# power.net
KiCad netlist of a schematic drawn in Altium Designer
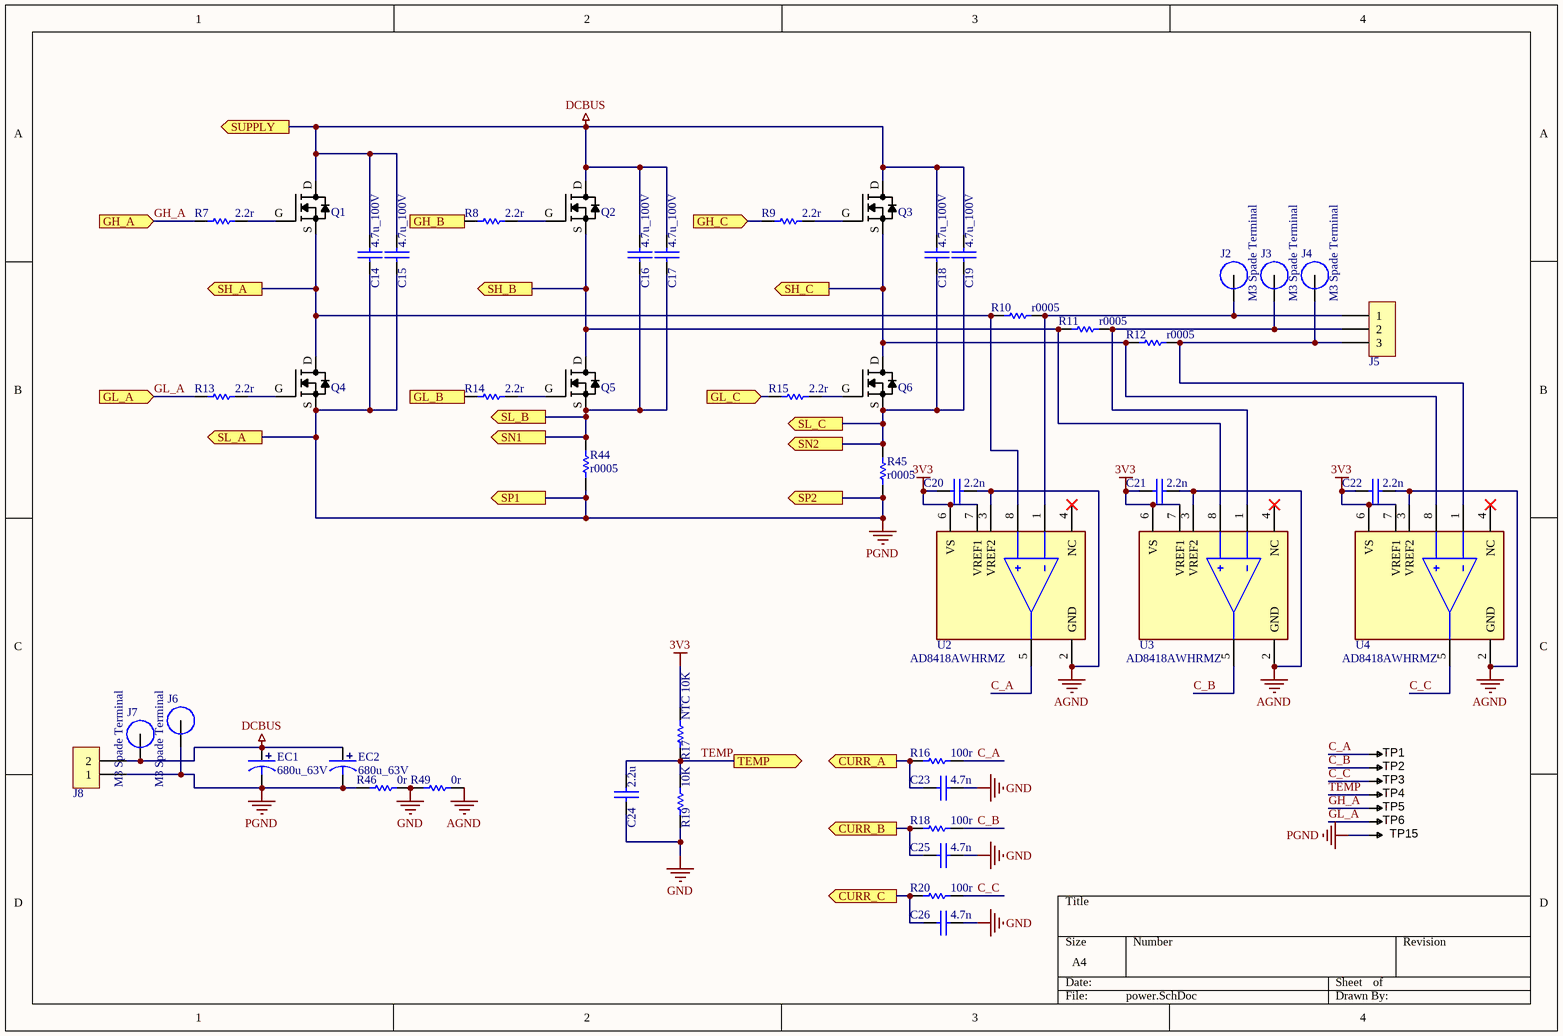
[diagram p0: power.SchDoc]

(export (version "E")
  (design (tool "Eeschema 10.0.6"))
  (components
    (comp (ref "C14")
      (value "4.7u_100V")
      (footprint "1206C")
      (description "无极性电容")
      (libsource (lib "电容") (part "CAP"))
    )
    (comp (ref "C15")
      (value "4.7u_100V")
      (footprint "1206C")
      (description "无极性电容")
      (libsource (lib "电容") (part "CAP"))
    )
    (comp (ref "C16")
      (value "4.7u_100V")
      (footprint "1206C")
      (description "无极性电容")
      (libsource (lib "电容") (part "CAP"))
    )
    (comp (ref "C17")
      (value "4.7u_100V")
      (footprint "1206C")
      (description "无极性电容")
      (libsource (lib "电容") (part "CAP"))
    )
    (comp (ref "C18")
      (value "4.7u_100V")
      (footprint "1206C")
      (description "无极性电容")
      (libsource (lib "电容") (part "CAP"))
    )
    (comp (ref "C19")
      (value "4.7u_100V")
      (footprint "1206C")
      (description "无极性电容")
      (libsource (lib "电容") (part "CAP"))
    )
    (comp (ref "C20")
      (value "2.2n")
      (footprint "0603C")
      (description "无极性电容")
      (libsource (lib "电容") (part "CAP"))
    )
    (comp (ref "C21")
      (value "2.2n")
      (footprint "0603C")
      (description "无极性电容")
      (libsource (lib "电容") (part "CAP"))
    )
    (comp (ref "C22")
      (value "2.2n")
      (footprint "0603C")
      (description "无极性电容")
      (libsource (lib "电容") (part "CAP"))
    )
    (comp (ref "C23")
      (value "4.7n")
      (footprint "0603C")
      (description "无极性电容")
      (libsource (lib "电容") (part "CAP"))
    )
    (comp (ref "C24")
      (value "2.2u")
      (footprint "0603C")
      (description "无极性电容")
      (libsource (lib "电容") (part "CAP"))
    )
    (comp (ref "C25")
      (value "4.7n")
      (footprint "0603C")
      (description "无极性电容")
      (libsource (lib "电容") (part "CAP"))
    )
    (comp (ref "C26")
      (value "4.7n")
      (footprint "0603C")
      (description "无极性电容")
      (libsource (lib "电容") (part "CAP"))
    )
    (comp (ref "EC1")
      (value "680u_63V")
      (footprint "DIP-EC5.0X12.5X25")
      (description "直插电解电容")
      (libsource (lib "电容") (part "DIP_ECAP"))
    )
    (comp (ref "EC2")
      (value "680u_63V")
      (footprint "DIP-EC5.0X12.5X25")
      (description "直插电解电容")
      (libsource (lib "电容") (part "DIP_ECAP"))
    )
    (comp (ref "J2")
      (value "M3 Spade Terminal")
      (footprint "M3 Spade Hole")
      (libsource (lib "two_ax_PCB") (part "M3 Spade Terminal"))
    )
    (comp (ref "J3")
      (value "M3 Spade Terminal")
      (footprint "M3 Spade Hole")
      (libsource (lib "two_ax_PCB") (part "M3 Spade Terminal"))
    )
    (comp (ref "J4")
      (value "M3 Spade Terminal")
      (footprint "M3 Spade Hole")
      (libsource (lib "two_ax_PCB") (part "M3 Spade Terminal"))
    )
    (comp (ref "J5")
      (value "1704936")
      (footprint "1704936")
      (description "CONN TERM BLOCK 3POS 7.62MM")
      (fields (field (name "MANUFACTURER") "Phoenix Contact") (field (name "VOLTAGE") "300V"))
      (libsource (lib "two_ax_PCB") (part "1704936"))
    )
    (comp (ref "J6")
      (value "M3 Spade Terminal")
      (footprint "M3 Spade Hole")
      (libsource (lib "two_ax_PCB") (part "M3 Spade Terminal"))
    )
    (comp (ref "J7")
      (value "M3 Spade Terminal")
      (footprint "M3 Spade Hole")
      (libsource (lib "two_ax_PCB") (part "M3 Spade Terminal"))
    )
    (comp (ref "J8")
      (value "1868076")
      (footprint "1868076")
      (description "CONN TERM BLOCK 2POS 7.62MM")
      (fields (field (name "MANUFACTURER") "Phoenix Contact") (field (name "VOLTAGE") "300V"))
      (libsource (lib "two_ax_PCB") (part "1868076"))
    )
    (comp (ref "Q1")
      (value "FILL_FOOTPRINT")
      (footprint "SO8FL_VIAS")
      (description "MOSFET N-CH 30V 13A SO8FL")
      (fields
        (field (name "MANUFACTURER") "ON Semiconductor")
        (field (name "MANUFACTURER PART NUMBER") "NTMFS4935NT1G")
      )
      (libsource (lib "two_ax_PCB") (part "NTMFS4935NT1G_1"))
    )
    (comp (ref "Q2")
      (value "FILL_FOOTPRINT")
      (footprint "SO8FL_VIAS")
      (description "MOSFET N-CH 30V 13A SO8FL")
      (fields
        (field (name "MANUFACTURER") "ON Semiconductor")
        (field (name "MANUFACTURER PART NUMBER") "NTMFS4935NT1G")
      )
      (libsource (lib "two_ax_PCB") (part "NTMFS4935NT1G_1"))
    )
    (comp (ref "Q3")
      (value "FILL_FOOTPRINT")
      (footprint "SO8FL_VIAS")
      (description "MOSFET N-CH 30V 13A SO8FL")
      (fields
        (field (name "MANUFACTURER") "ON Semiconductor")
        (field (name "MANUFACTURER PART NUMBER") "NTMFS4935NT1G")
      )
      (libsource (lib "two_ax_PCB") (part "NTMFS4935NT1G_1"))
    )
    (comp (ref "Q4")
      (value "FILL_FOOTPRINT")
      (footprint "SO8FL_VIAS")
      (description "MOSFET N-CH 30V 13A SO8FL")
      (fields
        (field (name "MANUFACTURER") "ON Semiconductor")
        (field (name "MANUFACTURER PART NUMBER") "NTMFS4935NT1G")
      )
      (libsource (lib "two_ax_PCB") (part "NTMFS4935NT1G_1"))
    )
    (comp (ref "Q5")
      (value "FILL_FOOTPRINT")
      (footprint "SO8FL_VIAS")
      (description "MOSFET N-CH 30V 13A SO8FL")
      (fields
        (field (name "MANUFACTURER") "ON Semiconductor")
        (field (name "MANUFACTURER PART NUMBER") "NTMFS4935NT1G")
      )
      (libsource (lib "two_ax_PCB") (part "NTMFS4935NT1G_1"))
    )
    (comp (ref "Q6")
      (value "FILL_FOOTPRINT")
      (footprint "SO8FL_VIAS")
      (description "MOSFET N-CH 30V 13A SO8FL")
      (fields
        (field (name "MANUFACTURER") "ON Semiconductor")
        (field (name "MANUFACTURER PART NUMBER") "NTMFS4935NT1G")
      )
      (libsource (lib "two_ax_PCB") (part "NTMFS4935NT1G_1"))
    )
    (comp (ref "R7") (value "2.2r") (footprint "0603R") (libsource (lib "电阻") (part "RES")))
    (comp (ref "R8") (value "2.2r") (footprint "0603R") (libsource (lib "电阻") (part "RES")))
    (comp (ref "R9") (value "2.2r") (footprint "0603R") (libsource (lib "电阻") (part "RES")))
    (comp (ref "R10") (value "r0005") (footprint "2512R") (libsource (lib "电阻") (part "RES")))
    (comp (ref "R11") (value "r0005") (footprint "2512R") (libsource (lib "电阻") (part "RES")))
    (comp (ref "R12") (value "r0005") (footprint "2512R") (libsource (lib "电阻") (part "RES")))
    (comp (ref "R13") (value "2.2r") (footprint "0603R") (libsource (lib "电阻") (part "RES")))
    (comp (ref "R14") (value "2.2r") (footprint "0603R") (libsource (lib "电阻") (part "RES")))
    (comp (ref "R15") (value "2.2r") (footprint "0603R") (libsource (lib "电阻") (part "RES")))
    (comp (ref "R16") (value "100r") (footprint "0603R") (libsource (lib "电阻") (part "RES")))
    (comp (ref "R17") (value "NTC 10K") (footprint "0603R") (libsource (lib "电阻") (part "RES")))
    (comp (ref "R18") (value "100r") (footprint "0603R") (libsource (lib "电阻") (part "RES")))
    (comp (ref "R19") (value "10K") (footprint "0603R") (libsource (lib "电阻") (part "RES")))
    (comp (ref "R20") (value "100r") (footprint "0603R") (libsource (lib "电阻") (part "RES")))
    (comp (ref "R44") (value "r0005") (footprint "2512R") (libsource (lib "电阻") (part "RES")))
    (comp (ref "R45") (value "r0005") (footprint "2512R") (libsource (lib "电阻") (part "RES")))
    (comp (ref "R46") (value "0r") (footprint "0603R") (libsource (lib "电阻") (part "RES")))
    (comp (ref "R49") (value "0r") (footprint "0603R") (libsource (lib "电阻") (part "RES")))
    (comp (ref "TP1")
      (value "TESTPOINT")
      (footprint "FIDUCIAL")
      (description "SMD test pin")
      (libsource (lib "two_ax_PCB") (part "TESTPOINT"))
    )
    (comp (ref "TP2")
      (value "TESTPOINT")
      (footprint "FIDUCIAL")
      (description "SMD test pin")
      (libsource (lib "two_ax_PCB") (part "TESTPOINT"))
    )
    (comp (ref "TP3")
      (value "TESTPOINT")
      (footprint "FIDUCIAL")
      (description "SMD test pin")
      (libsource (lib "two_ax_PCB") (part "TESTPOINT"))
    )
    (comp (ref "TP4")
      (value "TESTPOINT")
      (footprint "FIDUCIAL")
      (description "SMD test pin")
      (libsource (lib "two_ax_PCB") (part "TESTPOINT"))
    )
    (comp (ref "TP5")
      (value "TESTPOINT")
      (footprint "FIDUCIAL")
      (description "SMD test pin")
      (libsource (lib "two_ax_PCB") (part "TESTPOINT"))
    )
    (comp (ref "TP6")
      (value "TESTPOINT")
      (footprint "FIDUCIAL")
      (description "SMD test pin")
      (libsource (lib "two_ax_PCB") (part "TESTPOINT"))
    )
    (comp (ref "TP15")
      (value "TESTPOINT")
      (footprint "FIDUCIAL")
      (description "SMD test pin")
      (libsource (lib "two_ax_PCB") (part "TESTPOINT"))
    )
    (comp (ref "U2")
      (value "AD8418AWHRMZ")
      (footprint "FP-RM-8-IPC_A")
      (description "IC CURR SENSE 1 CIRCUIT 8MSOP")
      (libsource (lib "Altium Content Vault") (part "e0672f2e4abe77d2531f0930e625d4f"))
    )
    (comp (ref "U3")
      (value "AD8418AWHRMZ")
      (footprint "FP-RM-8-IPC_A")
      (description "IC CURR SENSE 1 CIRCUIT 8MSOP")
      (libsource (lib "Altium Content Vault") (part "e0672f2e4abe77d2531f0930e625d4f"))
    )
    (comp (ref "U4")
      (value "AD8418AWHRMZ")
      (footprint "FP-RM-8-IPC_A")
      (description "IC CURR SENSE 1 CIRCUIT 8MSOP")
      (libsource (lib "Altium Content Vault") (part "e0672f2e4abe77d2531f0930e625d4f"))
    )
  )
  (nets
    (net (code "1") (name "/CURR_A") (class "Default")
      (node (ref "C23") (pin "2") (pinfunction "2_2") (pintype "passive"))
      (node (ref "R16") (pin "2") (pinfunction "2_2") (pintype "passive"))
    )
    (net (code "2") (name "/CURR_B") (class "Default")
      (node (ref "C25") (pin "2") (pinfunction "2_2") (pintype "passive"))
      (node (ref "R18") (pin "2") (pinfunction "2_2") (pintype "passive"))
    )
    (net (code "3") (name "/CURR_C") (class "Default")
      (node (ref "C26") (pin "2") (pinfunction "2_2") (pintype "passive"))
      (node (ref "R20") (pin "2") (pinfunction "2_2") (pintype "passive"))
    )
    (net (code "4") (name "/C_A") (class "Default")
      (node (ref "R16") (pin "1") (pinfunction "1_1") (pintype "passive"))
      (node (ref "TP1") (pin "1") (pintype "passive"))
      (node (ref "U2") (pin "5") (pinfunction "OUT_5") (pintype "passive"))
    )
    (net (code "5") (name "/C_B") (class "Default")
      (node (ref "R18") (pin "1") (pinfunction "1_1") (pintype "passive"))
      (node (ref "TP2") (pin "1") (pintype "passive"))
      (node (ref "U3") (pin "5") (pinfunction "OUT_5") (pintype "passive"))
    )
    (net (code "6") (name "/C_C") (class "Default")
      (node (ref "R20") (pin "1") (pinfunction "1_1") (pintype "passive"))
      (node (ref "TP3") (pin "1") (pintype "passive"))
      (node (ref "U4") (pin "5") (pinfunction "OUT_5") (pintype "passive"))
    )
    (net (code "7") (name "/GH_A") (class "Default")
      (node (ref "R7") (pin "1") (pinfunction "1_1") (pintype "passive"))
      (node (ref "TP5") (pin "1") (pintype "passive"))
    )
    (net (code "8") (name "/GH_B") (class "Default")
      (node (ref "R8") (pin "1") (pinfunction "1_1") (pintype "passive"))
    )
    (net (code "9") (name "/GH_C") (class "Default")
      (node (ref "R9") (pin "1") (pinfunction "1_1") (pintype "passive"))
    )
    (net (code "10") (name "/GL_A") (class "Default")
      (node (ref "R13") (pin "1") (pinfunction "1_1") (pintype "passive"))
      (node (ref "TP6") (pin "1") (pintype "passive"))
    )
    (net (code "11") (name "/GL_B") (class "Default")
      (node (ref "R14") (pin "1") (pinfunction "1_1") (pintype "passive"))
    )
    (net (code "12") (name "/GL_C") (class "Default")
      (node (ref "R15") (pin "1") (pinfunction "1_1") (pintype "passive"))
    )
    (net (code "13") (name "/SH_A") (class "Default")
      (node (ref "Q1") (pin "S") (pinfunction "S_S") (pintype "passive"))
      (node (ref "Q4") (pin "D") (pinfunction "D_D") (pintype "passive"))
      (node (ref "R10") (pin "2") (pinfunction "2_2") (pintype "passive"))
      (node (ref "U2") (pin "8") (pinfunction "+IN_8") (pintype "tri_state"))
    )
    (net (code "14") (name "/SH_B") (class "Default")
      (node (ref "Q2") (pin "S") (pinfunction "S_S") (pintype "passive"))
      (node (ref "Q5") (pin "D") (pinfunction "D_D") (pintype "passive"))
      (node (ref "R11") (pin "2") (pinfunction "2_2") (pintype "passive"))
      (node (ref "U3") (pin "8") (pinfunction "+IN_8") (pintype "tri_state"))
    )
    (net (code "15") (name "/SH_C") (class "Default")
      (node (ref "Q3") (pin "S") (pinfunction "S_S") (pintype "passive"))
      (node (ref "Q6") (pin "D") (pinfunction "D_D") (pintype "passive"))
      (node (ref "R12") (pin "2") (pinfunction "2_2") (pintype "passive"))
      (node (ref "U4") (pin "8") (pinfunction "+IN_8") (pintype "tri_state"))
    )
    (net (code "16") (name "/SL_B") (class "Default")
      (node (ref "C16") (pin "1") (pinfunction "1_1") (pintype "passive"))
      (node (ref "C17") (pin "1") (pinfunction "1_1") (pintype "passive"))
      (node (ref "Q5") (pin "S") (pinfunction "S_S") (pintype "passive"))
      (node (ref "R44") (pin "1") (pinfunction "1_1") (pintype "passive"))
    )
    (net (code "17") (name "/SL_C") (class "Default")
      (node (ref "C18") (pin "1") (pinfunction "1_1") (pintype "passive"))
      (node (ref "C19") (pin "1") (pinfunction "1_1") (pintype "passive"))
      (node (ref "Q6") (pin "S") (pinfunction "S_S") (pintype "passive"))
      (node (ref "R45") (pin "1") (pinfunction "1_1") (pintype "passive"))
    )
    (net (code "18") (name "/TEMP") (class "Default")
      (node (ref "C24") (pin "2") (pinfunction "2_2") (pintype "passive"))
      (node (ref "R17") (pin "1") (pinfunction "1_1") (pintype "passive"))
      (node (ref "R19") (pin "2") (pinfunction "2_2") (pintype "passive"))
      (node (ref "TP4") (pin "1") (pintype "passive"))
    )
    (net (code "19") (name "3V3") (class "Default")
      (node (ref "C20") (pin "2") (pinfunction "2_2") (pintype "passive"))
      (node (ref "C21") (pin "2") (pinfunction "2_2") (pintype "passive"))
      (node (ref "C22") (pin "2") (pinfunction "2_2") (pintype "passive"))
      (node (ref "R17") (pin "2") (pinfunction "2_2") (pintype "passive"))
      (node (ref "U2") (pin "6") (pinfunction "VS_6") (pintype "power_in"))
      (node (ref "U2") (pin "7") (pinfunction "VREF1_7") (pintype "passive"))
      (node (ref "U3") (pin "6") (pinfunction "VS_6") (pintype "power_in"))
      (node (ref "U3") (pin "7") (pinfunction "VREF1_7") (pintype "passive"))
      (node (ref "U4") (pin "6") (pinfunction "VS_6") (pintype "power_in"))
      (node (ref "U4") (pin "7") (pinfunction "VREF1_7") (pintype "passive"))
    )
    (net (code "20") (name "AGND") (class "Default")
      (node (ref "C20") (pin "1") (pinfunction "1_1") (pintype "passive"))
      (node (ref "C21") (pin "1") (pinfunction "1_1") (pintype "passive"))
      (node (ref "C22") (pin "1") (pinfunction "1_1") (pintype "passive"))
      (node (ref "R49") (pin "1") (pinfunction "1_1") (pintype "passive"))
      (node (ref "U2") (pin "2") (pinfunction "GND_2") (pintype "power_in"))
      (node (ref "U2") (pin "3") (pinfunction "VREF2_3") (pintype "passive"))
      (node (ref "U3") (pin "2") (pinfunction "GND_2") (pintype "power_in"))
      (node (ref "U3") (pin "3") (pinfunction "VREF2_3") (pintype "passive"))
      (node (ref "U4") (pin "2") (pinfunction "GND_2") (pintype "power_in"))
      (node (ref "U4") (pin "3") (pinfunction "VREF2_3") (pintype "passive"))
    )
    (net (code "21") (name "DCBUS") (class "Default")
      (node (ref "C14") (pin "2") (pinfunction "2_2") (pintype "passive"))
      (node (ref "C15") (pin "2") (pinfunction "2_2") (pintype "passive"))
      (node (ref "C16") (pin "2") (pinfunction "2_2") (pintype "passive"))
      (node (ref "C17") (pin "2") (pinfunction "2_2") (pintype "passive"))
      (node (ref "C18") (pin "2") (pinfunction "2_2") (pintype "passive"))
      (node (ref "C19") (pin "2") (pinfunction "2_2") (pintype "passive"))
      (node (ref "EC1") (pin "1") (pinfunction "1_1") (pintype "passive"))
      (node (ref "EC2") (pin "1") (pinfunction "1_1") (pintype "passive"))
      (node (ref "J7") (pin "1") (pinfunction "1_1") (pintype "passive"))
      (node (ref "J8") (pin "2") (pinfunction "2_2") (pintype "passive"))
      (node (ref "Q1") (pin "D") (pinfunction "D_D") (pintype "passive"))
      (node (ref "Q2") (pin "D") (pinfunction "D_D") (pintype "passive"))
      (node (ref "Q3") (pin "D") (pinfunction "D_D") (pintype "passive"))
    )
    (net (code "22") (name "GND") (class "Default")
      (node (ref "C23") (pin "1") (pinfunction "1_1") (pintype "passive"))
      (node (ref "C24") (pin "1") (pinfunction "1_1") (pintype "passive"))
      (node (ref "C25") (pin "1") (pinfunction "1_1") (pintype "passive"))
      (node (ref "C26") (pin "1") (pinfunction "1_1") (pintype "passive"))
      (node (ref "R19") (pin "1") (pinfunction "1_1") (pintype "passive"))
      (node (ref "R46") (pin "1") (pinfunction "1_1") (pintype "passive"))
      (node (ref "R49") (pin "2") (pinfunction "2_2") (pintype "passive"))
    )
    (net (code "23") (name "Net-(Q1-PadG)") (class "Default")
      (node (ref "Q1") (pin "G") (pinfunction "G_G") (pintype "passive"))
      (node (ref "R7") (pin "2") (pinfunction "2_2") (pintype "passive"))
    )
    (net (code "24") (name "Net-(Q2-PadG)") (class "Default")
      (node (ref "Q2") (pin "G") (pinfunction "G_G") (pintype "passive"))
      (node (ref "R8") (pin "2") (pinfunction "2_2") (pintype "passive"))
    )
    (net (code "25") (name "Net-(Q3-PadG)") (class "Default")
      (node (ref "Q3") (pin "G") (pinfunction "G_G") (pintype "passive"))
      (node (ref "R9") (pin "2") (pinfunction "2_2") (pintype "passive"))
    )
    (net (code "26") (name "Net-(Q4-PadG)") (class "Default")
      (node (ref "Q4") (pin "G") (pinfunction "G_G") (pintype "passive"))
      (node (ref "R13") (pin "2") (pinfunction "2_2") (pintype "passive"))
    )
    (net (code "27") (name "Net-(Q5-PadG)") (class "Default")
      (node (ref "Q5") (pin "G") (pinfunction "G_G") (pintype "passive"))
      (node (ref "R14") (pin "2") (pinfunction "2_2") (pintype "passive"))
    )
    (net (code "28") (name "Net-(Q6-PadG)") (class "Default")
      (node (ref "Q6") (pin "G") (pinfunction "G_G") (pintype "passive"))
      (node (ref "R15") (pin "2") (pinfunction "2_2") (pintype "passive"))
    )
    (net (code "29") (name "Net-(U2--IN)") (class "Default")
      (node (ref "J2") (pin "1") (pinfunction "1_1") (pintype "passive"))
      (node (ref "J5") (pin "1") (pinfunction "1_1") (pintype "passive"))
      (node (ref "R10") (pin "1") (pinfunction "1_1") (pintype "passive"))
      (node (ref "U2") (pin "1") (pinfunction "-IN_1") (pintype "tri_state"))
    )
    (net (code "30") (name "Net-(U3--IN)") (class "Default")
      (node (ref "J3") (pin "1") (pinfunction "1_1") (pintype "passive"))
      (node (ref "J5") (pin "2") (pinfunction "2_2") (pintype "passive"))
      (node (ref "R11") (pin "1") (pinfunction "1_1") (pintype "passive"))
      (node (ref "U3") (pin "1") (pinfunction "-IN_1") (pintype "tri_state"))
    )
    (net (code "31") (name "Net-(U4--IN)") (class "Default")
      (node (ref "J4") (pin "1") (pinfunction "1_1") (pintype "passive"))
      (node (ref "J5") (pin "3") (pinfunction "3_3") (pintype "passive"))
      (node (ref "R12") (pin "1") (pinfunction "1_1") (pintype "passive"))
      (node (ref "U4") (pin "1") (pinfunction "-IN_1") (pintype "tri_state"))
    )
    (net (code "32") (name "PGND") (class "Default")
      (node (ref "C14") (pin "1") (pinfunction "1_1") (pintype "passive"))
      (node (ref "C15") (pin "1") (pinfunction "1_1") (pintype "passive"))
      (node (ref "EC1") (pin "2") (pinfunction "2_2") (pintype "passive"))
      (node (ref "EC2") (pin "2") (pinfunction "2_2") (pintype "passive"))
      (node (ref "J6") (pin "1") (pinfunction "1_1") (pintype "passive"))
      (node (ref "J8") (pin "1") (pinfunction "1_1") (pintype "passive"))
      (node (ref "Q4") (pin "S") (pinfunction "S_S") (pintype "passive"))
      (node (ref "R44") (pin "2") (pinfunction "2_2") (pintype "passive"))
      (node (ref "R45") (pin "2") (pinfunction "2_2") (pintype "passive"))
      (node (ref "R46") (pin "2") (pinfunction "2_2") (pintype "passive"))
      (node (ref "TP15") (pin "1") (pintype "passive"))
    )
    (net (code "33") (name "unconnected-(U2-NC-Pad4)") (class "Default")
      (node (ref "U2") (pin "4") (pinfunction "NC_4") (pintype "passive+no_connect"))
    )
    (net (code "34") (name "unconnected-(U3-NC-Pad4)") (class "Default")
      (node (ref "U3") (pin "4") (pinfunction "NC_4") (pintype "passive+no_connect"))
    )
    (net (code "35") (name "unconnected-(U4-NC-Pad4)") (class "Default")
      (node (ref "U4") (pin "4") (pinfunction "NC_4") (pintype "passive+no_connect"))
    )
  )
)
